# LPC2368_Breakout.net
KiCad netlist of a schematic drawn in EAGLE
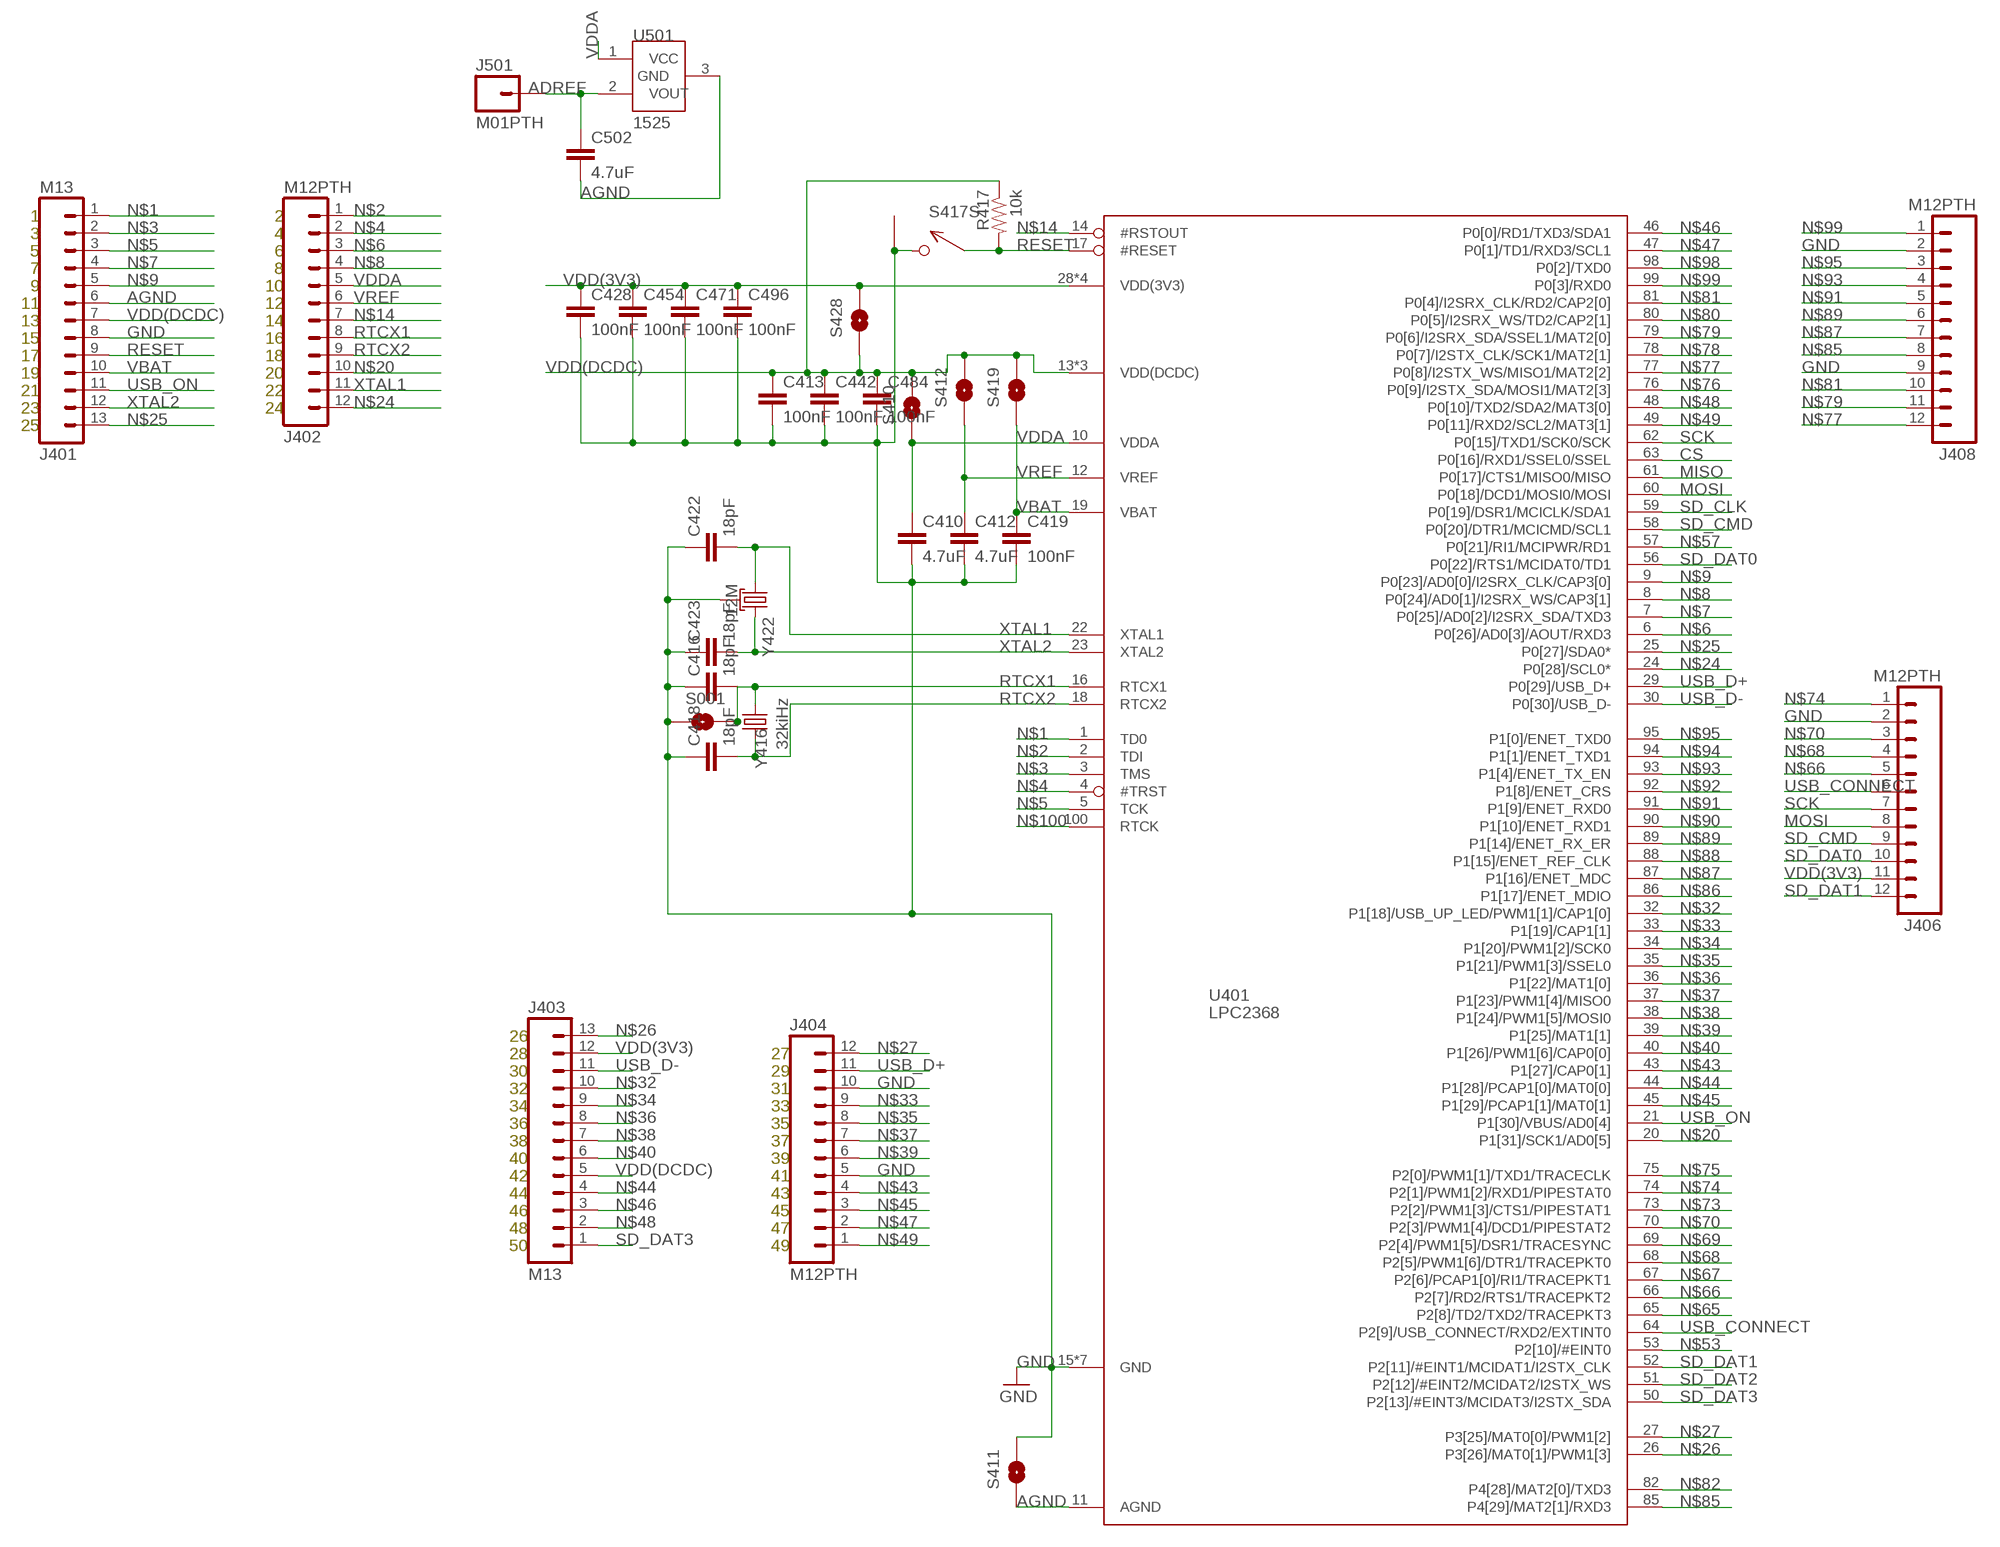
[diagram p0: schematic, sheet 1, part 1 of 2]
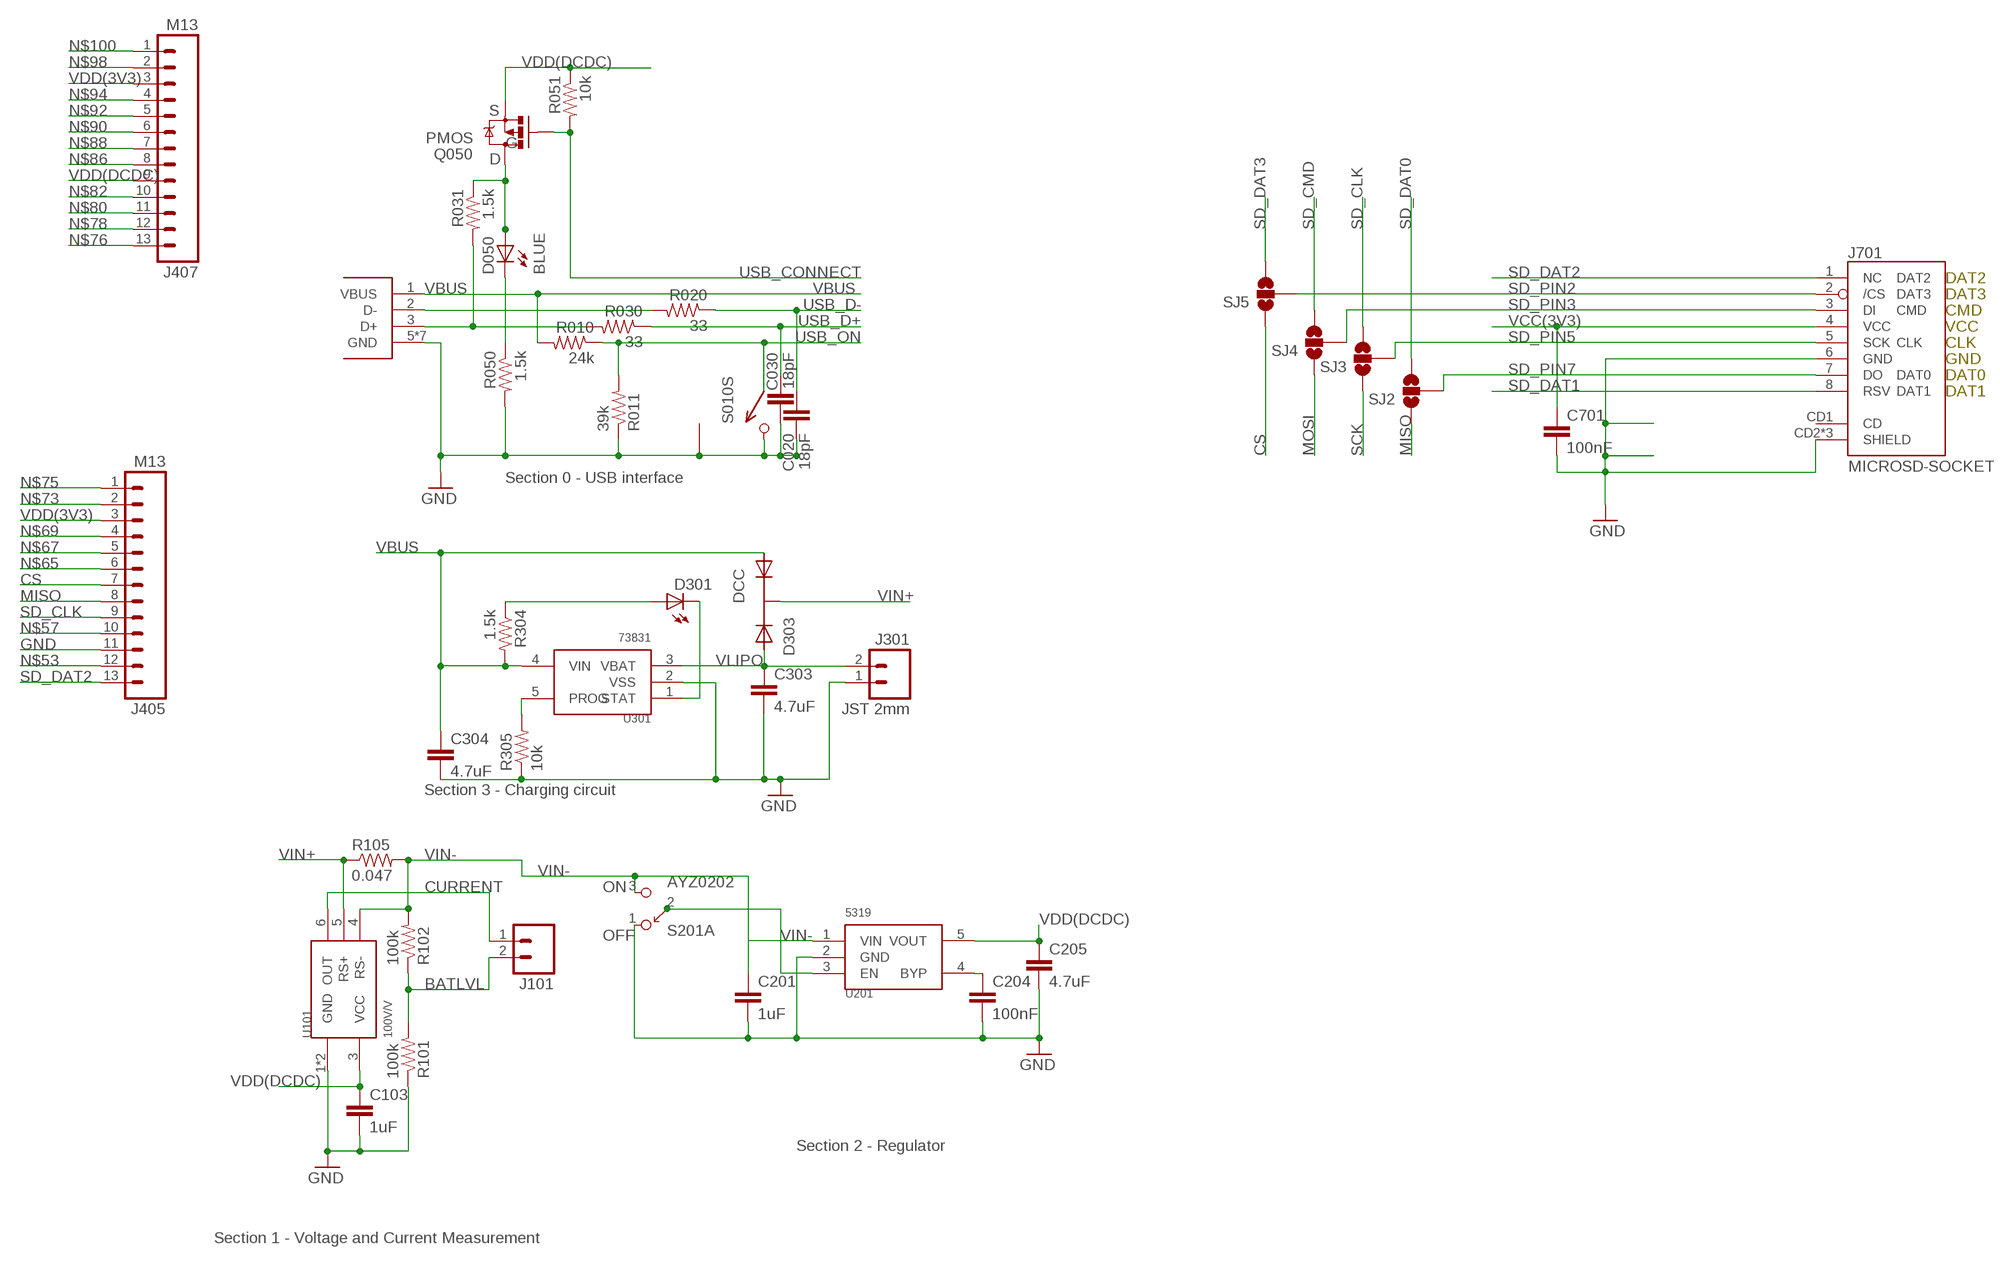
[diagram p1: schematic, sheet 1, part 2 of 2]

(export (version "E")
  (design (tool "Eeschema 10.0.6"))
  (components
    (comp (ref "C020")
      (value "18pF")
      (footprint "eagle-import:0402-CAP")
      (libsource (lib "eagle-import") (part "CAP0402-CAP"))
    )
    (comp (ref "C030")
      (value "18pF")
      (footprint "eagle-import:0402-CAP")
      (libsource (lib "eagle-import") (part "CAP0402-CAP"))
    )
    (comp (ref "C103")
      (value "1uF")
      (footprint "eagle-import:0402-CAP")
      (libsource (lib "eagle-import") (part "CAP0402-CAP"))
    )
    (comp (ref "C201")
      (value "1uF")
      (footprint "eagle-import:0402-CAP")
      (libsource (lib "eagle-import") (part "CAP0402-CAP"))
    )
    (comp (ref "C204")
      (value "100nF")
      (footprint "eagle-import:0402-CAP")
      (libsource (lib "eagle-import") (part "CAP0402-CAP"))
    )
    (comp (ref "C205")
      (value "4.7uF")
      (footprint "eagle-import:0402-CAP")
      (libsource (lib "eagle-import") (part "CAP0402-CAP"))
    )
    (comp (ref "C303")
      (value "4.7uF")
      (footprint "eagle-import:0402-CAP")
      (libsource (lib "eagle-import") (part "CAP0402-CAP"))
    )
    (comp (ref "C304")
      (value "4.7uF")
      (footprint "eagle-import:0402-CAP")
      (libsource (lib "eagle-import") (part "CAP0402-CAP"))
    )
    (comp (ref "C410")
      (value "4.7uF")
      (footprint "eagle-import:0402-CAP")
      (libsource (lib "eagle-import") (part "SparkFun-Passives_CAP0402-CAP"))
    )
    (comp (ref "C412")
      (value "4.7uF")
      (footprint "eagle-import:0402-CAP")
      (libsource (lib "eagle-import") (part "SparkFun-Passives_CAP0402-CAP"))
    )
    (comp (ref "C413")
      (value "100nF")
      (footprint "eagle-import:0402-CAP")
      (libsource (lib "eagle-import") (part "SparkFun-Passives_CAP0402-CAP"))
    )
    (comp (ref "C416")
      (value "18pF")
      (footprint "eagle-import:0402-CAP")
      (libsource (lib "eagle-import") (part "SparkFun-Passives_CAP0402-CAP"))
    )
    (comp (ref "C418")
      (value "18pF")
      (footprint "eagle-import:0402-CAP")
      (libsource (lib "eagle-import") (part "SparkFun-Passives_CAP0402-CAP"))
    )
    (comp (ref "C419")
      (value "100nF")
      (footprint "eagle-import:0402-CAP")
      (libsource (lib "eagle-import") (part "SparkFun-Passives_CAP0402-CAP"))
    )
    (comp (ref "C422")
      (value "18pF")
      (footprint "eagle-import:0402-CAP")
      (libsource (lib "eagle-import") (part "SparkFun-Passives_CAP0402-CAP"))
    )
    (comp (ref "C423")
      (value "18pF")
      (footprint "eagle-import:0402-CAP")
      (libsource (lib "eagle-import") (part "SparkFun-Passives_CAP0402-CAP"))
    )
    (comp (ref "C428")
      (value "100nF")
      (footprint "eagle-import:0402-CAP")
      (libsource (lib "eagle-import") (part "SparkFun-Passives_CAP0402-CAP"))
    )
    (comp (ref "C442")
      (value "100nF")
      (footprint "eagle-import:0402-CAP")
      (libsource (lib "eagle-import") (part "SparkFun-Passives_CAP0402-CAP"))
    )
    (comp (ref "C454")
      (value "100nF")
      (footprint "eagle-import:0402-CAP")
      (libsource (lib "eagle-import") (part "SparkFun-Passives_CAP0402-CAP"))
    )
    (comp (ref "C471")
      (value "100nF")
      (footprint "eagle-import:0402-CAP")
      (libsource (lib "eagle-import") (part "SparkFun-Passives_CAP0402-CAP"))
    )
    (comp (ref "C484")
      (value "100nF")
      (footprint "eagle-import:0402-CAP")
      (libsource (lib "eagle-import") (part "SparkFun-Passives_CAP0402-CAP"))
    )
    (comp (ref "C496")
      (value "100nF")
      (footprint "eagle-import:0402-CAP")
      (libsource (lib "eagle-import") (part "SparkFun-Passives_CAP0402-CAP"))
    )
    (comp (ref "C502")
      (value "4.7uF")
      (footprint "eagle-import:0402-CAP")
      (libsource (lib "eagle-import") (part "CAP0402-CAP"))
    )
    (comp (ref "C701")
      (value "100nF")
      (footprint "eagle-import:0402-CAP")
      (libsource (lib "eagle-import") (part "CAP0402-CAP"))
    )
    (comp (ref "D050")
      (value "BLUE")
      (footprint "eagle-import:LED-0603")
      (libsource (lib "eagle-import") (part "LED0603"))
    )
    (comp (ref "D301")
      (value "YELLOW")
      (footprint "eagle-import:LED-0603")
      (libsource (lib "eagle-import") (part "LED0603"))
    )
    (comp (ref "D303")
      (value "DCC")
      (footprint "eagle-import:SOT-23-3")
      (libsource (lib "eagle-import") (part "PMEG2005CT"))
    )
    (comp (ref "J001")
      (value "USB_MICROB_JST")
      (footprint "eagle-import:UB-MC5BR3-SD204-4S")
      (libsource (lib "eagle-import") (part "USB_MICROB_JST"))
    )
    (comp (ref "J101")
      (value "M02PTH")
      (footprint "eagle-import:1X02")
      (libsource (lib "eagle-import") (part "SparkFun-Connectors_M02PTH"))
    )
    (comp (ref "J301")
      (value "JST 2mm")
      (footprint "eagle-import:JST-2-SMD")
      (libsource (lib "eagle-import") (part "M02-JST-2MM-SMT"))
    )
    (comp (ref "J401")
      (value "M13")
      (footprint "eagle-import:1X13")
      (libsource (lib "eagle-import") (part "M13"))
    )
    (comp (ref "J402")
      (value "M12PTH")
      (footprint "eagle-import:1X12")
      (libsource (lib "eagle-import") (part "M12PTH"))
    )
    (comp (ref "J403")
      (value "M13")
      (footprint "eagle-import:1X13")
      (libsource (lib "eagle-import") (part "M13"))
    )
    (comp (ref "J404")
      (value "M12PTH")
      (footprint "eagle-import:1X12")
      (libsource (lib "eagle-import") (part "M12PTH"))
    )
    (comp (ref "J405")
      (value "M13")
      (footprint "eagle-import:1X13")
      (libsource (lib "eagle-import") (part "M13"))
    )
    (comp (ref "J406")
      (value "M12PTH")
      (footprint "eagle-import:1X12")
      (libsource (lib "eagle-import") (part "M12PTH"))
    )
    (comp (ref "J407")
      (value "M13")
      (footprint "eagle-import:1X13")
      (libsource (lib "eagle-import") (part "M13"))
    )
    (comp (ref "J408")
      (value "M12PTH")
      (footprint "eagle-import:1X12")
      (libsource (lib "eagle-import") (part "M12PTH"))
    )
    (comp (ref "J501")
      (value "M01PTH")
      (footprint "eagle-import:1X01")
      (libsource (lib "eagle-import") (part "M01PTH"))
    )
    (comp (ref "J701")
      (value "MICROSD-SOCKET")
      (footprint "eagle-import:MICROSD-SOCKET-PP")
      (libsource (lib "eagle-import") (part "MICROSD-SOCKET"))
    )
    (comp (ref "Q050")
      (value "PMOS")
      (footprint "eagle-import:SOT23-3")
      (libsource (lib "eagle-import") (part "MOSFET-PCHANNELSMD"))
    )
    (comp (ref "R010")
      (value "24k")
      (footprint "eagle-import:0402-RES")
      (libsource (lib "eagle-import") (part "RESISTOR0402-RES"))
    )
    (comp (ref "R011")
      (value "39k")
      (footprint "eagle-import:0402-RES")
      (libsource (lib "eagle-import") (part "RESISTOR0402-RES"))
    )
    (comp (ref "R020")
      (value "33")
      (footprint "eagle-import:0402-RES")
      (libsource (lib "eagle-import") (part "RESISTOR0402-RES"))
    )
    (comp (ref "R030")
      (value "33")
      (footprint "eagle-import:0402-RES")
      (libsource (lib "eagle-import") (part "RESISTOR0402-RES"))
    )
    (comp (ref "R031")
      (value "1.5k")
      (footprint "eagle-import:0402-RES")
      (libsource (lib "eagle-import") (part "RESISTOR0402-RES"))
    )
    (comp (ref "R050")
      (value "1.5k")
      (footprint "eagle-import:0402-RES")
      (libsource (lib "eagle-import") (part "RESISTOR0402-RES"))
    )
    (comp (ref "R051")
      (value "10k")
      (footprint "eagle-import:0402-RES")
      (libsource (lib "eagle-import") (part "RESISTOR0402-RES"))
    )
    (comp (ref "R101")
      (value "100k")
      (footprint "eagle-import:0402-RES")
      (libsource (lib "eagle-import") (part "RESISTOR0402-RES"))
    )
    (comp (ref "R102")
      (value "100k")
      (footprint "eagle-import:0402-RES")
      (libsource (lib "eagle-import") (part "RESISTOR0402-RES"))
    )
    (comp (ref "R105")
      (value "0.047")
      (footprint "eagle-import:0402-RES")
      (libsource (lib "eagle-import") (part "RESISTOR0402-RES"))
    )
    (comp (ref "R304")
      (value "1.5k")
      (footprint "eagle-import:0402-RES")
      (libsource (lib "eagle-import") (part "RESISTOR0402-RES"))
    )
    (comp (ref "R305")
      (value "10k")
      (footprint "eagle-import:0402-RES")
      (libsource (lib "eagle-import") (part "RESISTOR0402-RES"))
    )
    (comp (ref "R417")
      (value "10k")
      (footprint "eagle-import:0402-RES")
      (libsource (lib "eagle-import") (part "RESISTOR0402-RES"))
    )
    (comp (ref "S001")
      (value "SOLDERJUMPERNO")
      (footprint "eagle-import:SJ_2S-NO")
      (libsource (lib "eagle-import") (part "SOLDERJUMPERNO"))
    )
    (comp (ref "S010")
      (value "SPST")
      (footprint "eagle-import:B3U-1100P")
      (libsource (lib "eagle-import") (part "B3U-1100P"))
    )
    (comp (ref "S201")
      (value "AYZ0202")
      (footprint "eagle-import:AYZ0202")
      (libsource (lib "eagle-import") (part "AYZ0202"))
    )
    (comp (ref "S410")
      (value "SOLDERJUMPERNO")
      (footprint "eagle-import:SJ_2S-NO")
      (libsource (lib "eagle-import") (part "SOLDERJUMPERNO"))
    )
    (comp (ref "S411")
      (value "SOLDERJUMPERNO")
      (footprint "eagle-import:SJ_2S-NO")
      (libsource (lib "eagle-import") (part "SOLDERJUMPERNO"))
    )
    (comp (ref "S412")
      (value "SOLDERJUMPERNO")
      (footprint "eagle-import:SJ_2S-NO")
      (libsource (lib "eagle-import") (part "SOLDERJUMPERNO"))
    )
    (comp (ref "S417")
      (value "SPST")
      (footprint "eagle-import:B3U-1100P")
      (libsource (lib "eagle-import") (part "B3U-1100P"))
    )
    (comp (ref "S419")
      (value "SOLDERJUMPERNO")
      (footprint "eagle-import:SJ_2S-NO")
      (libsource (lib "eagle-import") (part "SOLDERJUMPERNO"))
    )
    (comp (ref "S428")
      (value "SOLDERJUMPERNO")
      (footprint "eagle-import:SJ_2S-NO")
      (libsource (lib "eagle-import") (part "SOLDERJUMPERNO"))
    )
    (comp (ref "SJ2")
      (value "SOLDERJUMPER_2WAYS")
      (footprint "eagle-import:SJ_3")
      (libsource (lib "eagle-import") (part "SOLDERJUMPER_2WAYS"))
    )
    (comp (ref "SJ3")
      (value "SOLDERJUMPER_2WAYS")
      (footprint "eagle-import:SJ_3")
      (libsource (lib "eagle-import") (part "SOLDERJUMPER_2WAYS"))
    )
    (comp (ref "SJ4")
      (value "SOLDERJUMPER_2WAYS")
      (footprint "eagle-import:SJ_3")
      (libsource (lib "eagle-import") (part "SOLDERJUMPER_2WAYS"))
    )
    (comp (ref "SJ5")
      (value "SOLDERJUMPER_2WAYS")
      (footprint "eagle-import:SJ_3")
      (libsource (lib "eagle-import") (part "SOLDERJUMPER_2WAYS"))
    )
    (comp (ref "U101")
      (value "100V/V")
      (footprint "eagle-import:SOT-23-6")
      (libsource (lib "eagle-import") (part "MAX4173"))
    )
    (comp (ref "U201")
      (value "5319")
      (footprint "eagle-import:SOT-23-5")
      (libsource (lib "eagle-import") (part "MIC5319D5"))
    )
    (comp (ref "U301")
      (value "73831")
      (footprint "eagle-import:SOT-23-5")
      (libsource (lib "eagle-import") (part "MCP73831"))
    )
    (comp (ref "U401")
      (value "LPC2368")
      (footprint "eagle-import:LQFP100")
      (libsource (lib "eagle-import") (part "LPC2368"))
    )
    (comp (ref "U501")
      (value "1525")
      (footprint "eagle-import:SOT-23-3")
      (libsource (lib "eagle-import") (part "MCP1525"))
    )
    (comp (ref "Y416")
      (value "32kiHz")
      (footprint "eagle-import:ABS06")
      (libsource (lib "eagle-import") (part "ABS06"))
    )
    (comp (ref "Y422")
      (value "12M")
      (footprint "eagle-import:CRYSTAL_SMD")
      (libsource (lib "eagle-import") (part "TSX-3225"))
    )
  )
  (nets
    (net (code "1") (name "/ADREF") (class "Default")
      (node (ref "C502") (pin "1") (pinfunction "1_1") (pintype "passive"))
      (node (ref "J501") (pin "1") (pinfunction "1_1") (pintype "passive"))
      (node (ref "U501") (pin "2") (pinfunction "VOUT_2") (pintype "bidirectional"))
    )
    (net (code "2") (name "/AGND") (class "Default")
      (node (ref "C502") (pin "2") (pinfunction "2_2") (pintype "passive"))
      (node (ref "J401") (pin "6") (pinfunction "6_6") (pintype "passive"))
      (node (ref "S411") (pin "1") (pinfunction "1_1") (pintype "passive"))
      (node (ref "U401") (pin "11") (pinfunction "AGND_11") (pintype "bidirectional"))
      (node (ref "U501") (pin "3") (pinfunction "GND_3") (pintype "bidirectional"))
    )
    (net (code "3") (name "/BATLVL") (class "Default")
      (node (ref "J101") (pin "2") (pinfunction "2_2") (pintype "passive"))
      (node (ref "R101") (pin "2") (pinfunction "2_2") (pintype "passive"))
      (node (ref "R102") (pin "1") (pinfunction "1_1") (pintype "passive"))
    )
    (net (code "4") (name "/CS") (class "Default")
      (node (ref "J405") (pin "7") (pinfunction "7_7") (pintype "passive"))
      (node (ref "SJ5") (pin "1") (pinfunction "1_1") (pintype "passive"))
      (node (ref "U401") (pin "63") (pinfunction "P0[16]/RXD1/SSEL0/SSEL_63") (pintype "bidirectional"))
    )
    (net (code "5") (name "/CURRENT") (class "Default")
      (node (ref "J101") (pin "1") (pinfunction "1_1") (pintype "passive"))
      (node (ref "U101") (pin "6") (pinfunction "OUT_6") (pintype "bidirectional"))
    )
    (net (code "6") (name "/MISO") (class "Default")
      (node (ref "J405") (pin "8") (pinfunction "8_8") (pintype "passive"))
      (node (ref "SJ2") (pin "1") (pinfunction "1_1") (pintype "passive"))
      (node (ref "U401") (pin "61") (pinfunction "P0[17]/CTS1/MISO0/MISO_61") (pintype "bidirectional"))
    )
    (net (code "7") (name "/MOSI") (class "Default")
      (node (ref "J406") (pin "8") (pinfunction "8_8") (pintype "passive"))
      (node (ref "SJ4") (pin "1") (pinfunction "1_1") (pintype "passive"))
      (node (ref "U401") (pin "60") (pinfunction "P0[18]/DCD1/MOSI0/MOSI_60") (pintype "bidirectional"))
    )
    (net (code "8") (name "/N$1") (class "Default")
      (node (ref "J401") (pin "1") (pinfunction "1_1") (pintype "passive"))
      (node (ref "U401") (pin "1") (pinfunction "TD0_1") (pintype "bidirectional"))
    )
    (net (code "9") (name "/N$2") (class "Default")
      (node (ref "J402") (pin "1") (pinfunction "1_1") (pintype "passive"))
      (node (ref "U401") (pin "2") (pinfunction "TDI_2") (pintype "bidirectional"))
    )
    (net (code "10") (name "/N$3") (class "Default")
      (node (ref "J401") (pin "2") (pinfunction "2_2") (pintype "passive"))
      (node (ref "U401") (pin "3") (pinfunction "TMS_3") (pintype "bidirectional"))
    )
    (net (code "11") (name "/N$4") (class "Default")
      (node (ref "J402") (pin "2") (pinfunction "2_2") (pintype "passive"))
      (node (ref "U401") (pin "4") (pinfunction "#TRST_4") (pintype "bidirectional"))
    )
    (net (code "12") (name "/N$5") (class "Default")
      (node (ref "J401") (pin "3") (pinfunction "3_3") (pintype "passive"))
      (node (ref "U401") (pin "5") (pinfunction "TCK_5") (pintype "bidirectional"))
    )
    (net (code "13") (name "/N$6") (class "Default")
      (node (ref "J402") (pin "3") (pinfunction "3_3") (pintype "passive"))
      (node (ref "U401") (pin "6") (pinfunction "P0[26]/AD0[3]/AOUT/RXD3_6") (pintype "bidirectional"))
    )
    (net (code "14") (name "/N$7") (class "Default")
      (node (ref "J401") (pin "4") (pinfunction "4_4") (pintype "passive"))
      (node (ref "U401") (pin "7") (pinfunction "P0[25]/AD0[2]/I2SRX_SDA/TXD3_7") (pintype "bidirectional"))
    )
    (net (code "15") (name "/N$8") (class "Default")
      (node (ref "J402") (pin "4") (pinfunction "4_4") (pintype "passive"))
      (node (ref "U401") (pin "8") (pinfunction "P0[24]/AD0[1]/I2SRX_WS/CAP3[1]_8") (pintype "bidirectional"))
    )
    (net (code "16") (name "/N$9") (class "Default")
      (node (ref "J401") (pin "5") (pinfunction "5_5") (pintype "passive"))
      (node (ref "U401") (pin "9") (pinfunction "P0[23]/AD0[0]/I2SRX_CLK/CAP3[0]_9") (pintype "bidirectional"))
    )
    (net (code "17") (name "/N$14") (class "Default")
      (node (ref "J402") (pin "7") (pinfunction "7_7") (pintype "passive"))
      (node (ref "U401") (pin "14") (pinfunction "#RSTOUT_14") (pintype "bidirectional"))
    )
    (net (code "18") (name "/N$20") (class "Default")
      (node (ref "J402") (pin "10") (pinfunction "10_10") (pintype "passive"))
      (node (ref "U401") (pin "20") (pinfunction "P1[31]/SCK1/AD0[5]_20") (pintype "bidirectional"))
    )
    (net (code "19") (name "/N$24") (class "Default")
      (node (ref "J402") (pin "12") (pinfunction "12_12") (pintype "passive"))
      (node (ref "U401") (pin "24") (pinfunction "P0[28]/SCL0*_24") (pintype "bidirectional"))
    )
    (net (code "20") (name "/N$25") (class "Default")
      (node (ref "J401") (pin "13") (pinfunction "13_13") (pintype "passive"))
      (node (ref "U401") (pin "25") (pinfunction "P0[27]/SDA0*_25") (pintype "bidirectional"))
    )
    (net (code "21") (name "/N$26") (class "Default")
      (node (ref "J403") (pin "13") (pinfunction "13_13") (pintype "passive"))
      (node (ref "U401") (pin "26") (pinfunction "P3[26]/MAT0[1]/PWM1[3]_26") (pintype "bidirectional"))
    )
    (net (code "22") (name "/N$27") (class "Default")
      (node (ref "J404") (pin "12") (pinfunction "12_12") (pintype "passive"))
      (node (ref "U401") (pin "27") (pinfunction "P3[25]/MAT0[0]/PWM1[2]_27") (pintype "bidirectional"))
    )
    (net (code "23") (name "/N$32") (class "Default")
      (node (ref "J403") (pin "10") (pinfunction "10_10") (pintype "passive"))
      (node (ref "U401") (pin "32") (pinfunction "P1[18]/USB_UP_LED/PWM1[1]/CAP1[0]_32") (pintype "bidirectional"))
    )
    (net (code "24") (name "/N$33") (class "Default")
      (node (ref "J404") (pin "9") (pinfunction "9_9") (pintype "passive"))
      (node (ref "U401") (pin "33") (pinfunction "P1[19]/CAP1[1]_33") (pintype "bidirectional"))
    )
    (net (code "25") (name "/N$34") (class "Default")
      (node (ref "J403") (pin "9") (pinfunction "9_9") (pintype "passive"))
      (node (ref "U401") (pin "34") (pinfunction "P1[20]/PWM1[2]/SCK0_34") (pintype "bidirectional"))
    )
    (net (code "26") (name "/N$35") (class "Default")
      (node (ref "J404") (pin "8") (pinfunction "8_8") (pintype "passive"))
      (node (ref "U401") (pin "35") (pinfunction "P1[21]/PWM1[3]/SSEL0_35") (pintype "bidirectional"))
    )
    (net (code "27") (name "/N$36") (class "Default")
      (node (ref "J403") (pin "8") (pinfunction "8_8") (pintype "passive"))
      (node (ref "U401") (pin "36") (pinfunction "P1[22]/MAT1[0]_36") (pintype "bidirectional"))
    )
    (net (code "28") (name "/N$37") (class "Default")
      (node (ref "J404") (pin "7") (pinfunction "7_7") (pintype "passive"))
      (node (ref "U401") (pin "37") (pinfunction "P1[23]/PWM1[4]/MISO0_37") (pintype "bidirectional"))
    )
    (net (code "29") (name "/N$38") (class "Default")
      (node (ref "J403") (pin "7") (pinfunction "7_7") (pintype "passive"))
      (node (ref "U401") (pin "38") (pinfunction "P1[24]/PWM1[5]/MOSI0_38") (pintype "bidirectional"))
    )
    (net (code "30") (name "/N$39") (class "Default")
      (node (ref "J404") (pin "6") (pinfunction "6_6") (pintype "passive"))
      (node (ref "U401") (pin "39") (pinfunction "P1[25]/MAT1[1]_39") (pintype "bidirectional"))
    )
    (net (code "31") (name "/N$40") (class "Default")
      (node (ref "J403") (pin "6") (pinfunction "6_6") (pintype "passive"))
      (node (ref "U401") (pin "40") (pinfunction "P1[26]/PWM1[6]/CAP0[0]_40") (pintype "bidirectional"))
    )
    (net (code "32") (name "/N$43") (class "Default")
      (node (ref "J404") (pin "4") (pinfunction "4_4") (pintype "passive"))
      (node (ref "U401") (pin "43") (pinfunction "P1[27]/CAP0[1]_43") (pintype "bidirectional"))
    )
    (net (code "33") (name "/N$44") (class "Default")
      (node (ref "J403") (pin "4") (pinfunction "4_4") (pintype "passive"))
      (node (ref "U401") (pin "44") (pinfunction "P1[28]/PCAP1[0]/MAT0[0]_44") (pintype "bidirectional"))
    )
    (net (code "34") (name "/N$45") (class "Default")
      (node (ref "J404") (pin "3") (pinfunction "3_3") (pintype "passive"))
      (node (ref "U401") (pin "45") (pinfunction "P1[29]/PCAP1[1]/MAT0[1]_45") (pintype "bidirectional"))
    )
    (net (code "35") (name "/N$46") (class "Default")
      (node (ref "J403") (pin "3") (pinfunction "3_3") (pintype "passive"))
      (node (ref "U401") (pin "46") (pinfunction "P0[0]/RD1/TXD3/SDA1_46") (pintype "bidirectional"))
    )
    (net (code "36") (name "/N$47") (class "Default")
      (node (ref "J404") (pin "2") (pinfunction "2_2") (pintype "passive"))
      (node (ref "U401") (pin "47") (pinfunction "P0[1]/TD1/RXD3/SCL1_47") (pintype "bidirectional"))
    )
    (net (code "37") (name "/N$48") (class "Default")
      (node (ref "J403") (pin "2") (pinfunction "2_2") (pintype "passive"))
      (node (ref "U401") (pin "48") (pinfunction "P0[10]/TXD2/SDA2/MAT3[0]_48") (pintype "bidirectional"))
    )
    (net (code "38") (name "/N$49") (class "Default")
      (node (ref "J404") (pin "1") (pinfunction "1_1") (pintype "passive"))
      (node (ref "U401") (pin "49") (pinfunction "P0[11]/RXD2/SCL2/MAT3[1]_49") (pintype "bidirectional"))
    )
    (net (code "39") (name "/N$53") (class "Default")
      (node (ref "J405") (pin "12") (pinfunction "12_12") (pintype "passive"))
      (node (ref "U401") (pin "53") (pinfunction "P2[10]/#EINT0_53") (pintype "bidirectional"))
    )
    (net (code "40") (name "/N$57") (class "Default")
      (node (ref "J405") (pin "10") (pinfunction "10_10") (pintype "passive"))
      (node (ref "U401") (pin "57") (pinfunction "P0[21]/RI1/MCIPWR/RD1_57") (pintype "bidirectional"))
    )
    (net (code "41") (name "/N$65") (class "Default")
      (node (ref "J405") (pin "6") (pinfunction "6_6") (pintype "passive"))
      (node (ref "U401") (pin "65") (pinfunction "P2[8]/TD2/TXD2/TRACEPKT3_65") (pintype "bidirectional"))
    )
    (net (code "42") (name "/N$66") (class "Default")
      (node (ref "J406") (pin "5") (pinfunction "5_5") (pintype "passive"))
      (node (ref "U401") (pin "66") (pinfunction "P2[7]/RD2/RTS1/TRACEPKT2_66") (pintype "bidirectional"))
    )
    (net (code "43") (name "/N$67") (class "Default")
      (node (ref "J405") (pin "5") (pinfunction "5_5") (pintype "passive"))
      (node (ref "U401") (pin "67") (pinfunction "P2[6]/PCAP1[0]/RI1/TRACEPKT1_67") (pintype "bidirectional"))
    )
    (net (code "44") (name "/N$68") (class "Default")
      (node (ref "J406") (pin "4") (pinfunction "4_4") (pintype "passive"))
      (node (ref "U401") (pin "68") (pinfunction "P2[5]/PWM1[6]/DTR1/TRACEPKT0_68") (pintype "bidirectional"))
    )
    (net (code "45") (name "/N$69") (class "Default")
      (node (ref "J405") (pin "4") (pinfunction "4_4") (pintype "passive"))
      (node (ref "U401") (pin "69") (pinfunction "P2[4]/PWM1[5]/DSR1/TRACESYNC_69") (pintype "bidirectional"))
    )
    (net (code "46") (name "/N$70") (class "Default")
      (node (ref "J406") (pin "3") (pinfunction "3_3") (pintype "passive"))
      (node (ref "U401") (pin "70") (pinfunction "P2[3]/PWM1[4]/DCD1/PIPESTAT2_70") (pintype "bidirectional"))
    )
    (net (code "47") (name "/N$73") (class "Default")
      (node (ref "J405") (pin "2") (pinfunction "2_2") (pintype "passive"))
      (node (ref "U401") (pin "73") (pinfunction "P2[2]/PWM1[3]/CTS1/PIPESTAT1_73") (pintype "bidirectional"))
    )
    (net (code "48") (name "/N$74") (class "Default")
      (node (ref "J406") (pin "1") (pinfunction "1_1") (pintype "passive"))
      (node (ref "U401") (pin "74") (pinfunction "P2[1]/PWM1[2]/RXD1/PIPESTAT0_74") (pintype "bidirectional"))
    )
    (net (code "49") (name "/N$75") (class "Default")
      (node (ref "J405") (pin "1") (pinfunction "1_1") (pintype "passive"))
      (node (ref "U401") (pin "75") (pinfunction "P2[0]/PWM1[1]/TXD1/TRACECLK_75") (pintype "bidirectional"))
    )
    (net (code "50") (name "/N$76") (class "Default")
      (node (ref "J407") (pin "13") (pinfunction "13_13") (pintype "passive"))
      (node (ref "U401") (pin "76") (pinfunction "P0[9]/I2STX_SDA/MOSI1/MAT2[3]_76") (pintype "bidirectional"))
    )
    (net (code "51") (name "/N$77") (class "Default")
      (node (ref "J408") (pin "12") (pinfunction "12_12") (pintype "passive"))
      (node (ref "U401") (pin "77") (pinfunction "P0[8]/I2STX_WS/MISO1/MAT2[2]_77") (pintype "bidirectional"))
    )
    (net (code "52") (name "/N$78") (class "Default")
      (node (ref "J407") (pin "12") (pinfunction "12_12") (pintype "passive"))
      (node (ref "U401") (pin "78") (pinfunction "P0[7]/I2STX_CLK/SCK1/MAT2[1]_78") (pintype "bidirectional"))
    )
    (net (code "53") (name "/N$79") (class "Default")
      (node (ref "J408") (pin "11") (pinfunction "11_11") (pintype "passive"))
      (node (ref "U401") (pin "79") (pinfunction "P0[6]/I2SRX_SDA/SSEL1/MAT2[0]_79") (pintype "bidirectional"))
    )
    (net (code "54") (name "/N$80") (class "Default")
      (node (ref "J407") (pin "11") (pinfunction "11_11") (pintype "passive"))
      (node (ref "U401") (pin "80") (pinfunction "P0[5]/I2SRX_WS/TD2/CAP2[1]_80") (pintype "bidirectional"))
    )
    (net (code "55") (name "/N$81") (class "Default")
      (node (ref "J408") (pin "10") (pinfunction "10_10") (pintype "passive"))
      (node (ref "U401") (pin "81") (pinfunction "P0[4]/I2SRX_CLK/RD2/CAP2[0]_81") (pintype "bidirectional"))
    )
    (net (code "56") (name "/N$82") (class "Default")
      (node (ref "J407") (pin "10") (pinfunction "10_10") (pintype "passive"))
      (node (ref "U401") (pin "82") (pinfunction "P4[28]/MAT2[0]/TXD3_82") (pintype "bidirectional"))
    )
    (net (code "57") (name "/N$85") (class "Default")
      (node (ref "J408") (pin "8") (pinfunction "8_8") (pintype "passive"))
      (node (ref "U401") (pin "85") (pinfunction "P4[29]/MAT2[1]/RXD3_85") (pintype "bidirectional"))
    )
    (net (code "58") (name "/N$86") (class "Default")
      (node (ref "J407") (pin "8") (pinfunction "8_8") (pintype "passive"))
      (node (ref "U401") (pin "86") (pinfunction "P1[17]/ENET_MDIO_86") (pintype "bidirectional"))
    )
    (net (code "59") (name "/N$87") (class "Default")
      (node (ref "J408") (pin "7") (pinfunction "7_7") (pintype "passive"))
      (node (ref "U401") (pin "87") (pinfunction "P1[16]/ENET_MDC_87") (pintype "bidirectional"))
    )
    (net (code "60") (name "/N$88") (class "Default")
      (node (ref "J407") (pin "7") (pinfunction "7_7") (pintype "passive"))
      (node (ref "U401") (pin "88") (pinfunction "P1[15]/ENET_REF_CLK_88") (pintype "bidirectional"))
    )
    (net (code "61") (name "/N$89") (class "Default")
      (node (ref "J408") (pin "6") (pinfunction "6_6") (pintype "passive"))
      (node (ref "U401") (pin "89") (pinfunction "P1[14]/ENET_RX_ER_89") (pintype "bidirectional"))
    )
    (net (code "62") (name "/N$90") (class "Default")
      (node (ref "J407") (pin "6") (pinfunction "6_6") (pintype "passive"))
      (node (ref "U401") (pin "90") (pinfunction "P1[10]/ENET_RXD1_90") (pintype "bidirectional"))
    )
    (net (code "63") (name "/N$91") (class "Default")
      (node (ref "J408") (pin "5") (pinfunction "5_5") (pintype "passive"))
      (node (ref "U401") (pin "91") (pinfunction "P1[9]/ENET_RXD0_91") (pintype "bidirectional"))
    )
    (net (code "64") (name "/N$92") (class "Default")
      (node (ref "J407") (pin "5") (pinfunction "5_5") (pintype "passive"))
      (node (ref "U401") (pin "92") (pinfunction "P1[8]/ENET_CRS_92") (pintype "bidirectional"))
    )
    (net (code "65") (name "/N$93") (class "Default")
      (node (ref "J408") (pin "4") (pinfunction "4_4") (pintype "passive"))
      (node (ref "U401") (pin "93") (pinfunction "P1[4]/ENET_TX_EN_93") (pintype "bidirectional"))
    )
    (net (code "66") (name "/N$94") (class "Default")
      (node (ref "J407") (pin "4") (pinfunction "4_4") (pintype "passive"))
      (node (ref "U401") (pin "94") (pinfunction "P1[1]/ENET_TXD1_94") (pintype "bidirectional"))
    )
    (net (code "67") (name "/N$95") (class "Default")
      (node (ref "J408") (pin "3") (pinfunction "3_3") (pintype "passive"))
      (node (ref "U401") (pin "95") (pinfunction "P1[0]/ENET_TXD0_95") (pintype "bidirectional"))
    )
    (net (code "68") (name "/N$98") (class "Default")
      (node (ref "J407") (pin "2") (pinfunction "2_2") (pintype "passive"))
      (node (ref "U401") (pin "98") (pinfunction "P0[2]/TXD0_98") (pintype "bidirectional"))
    )
    (net (code "69") (name "/N$99") (class "Default")
      (node (ref "J408") (pin "1") (pinfunction "1_1") (pintype "passive"))
      (node (ref "U401") (pin "99") (pinfunction "P0[3]/RXD0_99") (pintype "bidirectional"))
    )
    (net (code "70") (name "/N$100") (class "Default")
      (node (ref "J407") (pin "1") (pinfunction "1_1") (pintype "passive"))
      (node (ref "U401") (pin "100") (pinfunction "RTCK_100") (pintype "bidirectional"))
    )
    (net (code "71") (name "/RESET") (class "Default")
      (node (ref "J401") (pin "9") (pinfunction "9_9") (pintype "passive"))
      (node (ref "R417") (pin "2") (pinfunction "2_2") (pintype "passive"))
      (node (ref "S417") (pin "P$1") (pinfunction "1_P$1") (pintype "bidirectional"))
      (node (ref "U401") (pin "17") (pinfunction "#RESET_17") (pintype "bidirectional"))
    )
    (net (code "72") (name "/RTCX1") (class "Default")
      (node (ref "C416") (pin "2") (pinfunction "2_2") (pintype "passive"))
      (node (ref "J402") (pin "8") (pinfunction "8_8") (pintype "passive"))
      (node (ref "S001") (pin "2") (pinfunction "2_2") (pintype "passive"))
      (node (ref "U401") (pin "16") (pinfunction "RTCX1_16") (pintype "bidirectional"))
      (node (ref "Y416") (pin "1") (pinfunction "1_1") (pintype "passive"))
    )
    (net (code "73") (name "/RTCX2") (class "Default")
      (node (ref "C418") (pin "2") (pinfunction "2_2") (pintype "passive"))
      (node (ref "J402") (pin "9") (pinfunction "9_9") (pintype "passive"))
      (node (ref "U401") (pin "18") (pinfunction "RTCX2_18") (pintype "bidirectional"))
      (node (ref "Y416") (pin "2") (pinfunction "2_2") (pintype "passive"))
    )
    (net (code "74") (name "/SCK") (class "Default")
      (node (ref "J406") (pin "7") (pinfunction "7_7") (pintype "passive"))
      (node (ref "SJ3") (pin "1") (pinfunction "1_1") (pintype "passive"))
      (node (ref "U401") (pin "62") (pinfunction "P0[15]/TXD1/SCK0/SCK_62") (pintype "bidirectional"))
    )
    (net (code "75") (name "/SD_CLK") (class "Default")
      (node (ref "J405") (pin "9") (pinfunction "9_9") (pintype "passive"))
      (node (ref "SJ3") (pin "3") (pinfunction "3_3") (pintype "passive"))
      (node (ref "U401") (pin "59") (pinfunction "P0[19]/DSR1/MCICLK/SDA1_59") (pintype "bidirectional"))
    )
    (net (code "76") (name "/SD_CMD") (class "Default")
      (node (ref "J406") (pin "9") (pinfunction "9_9") (pintype "passive"))
      (node (ref "SJ4") (pin "3") (pinfunction "3_3") (pintype "passive"))
      (node (ref "U401") (pin "58") (pinfunction "P0[20]/DTR1/MCICMD/SCL1_58") (pintype "bidirectional"))
    )
    (net (code "77") (name "/SD_DAT0") (class "Default")
      (node (ref "J406") (pin "10") (pinfunction "10_10") (pintype "passive"))
      (node (ref "SJ2") (pin "3") (pinfunction "3_3") (pintype "passive"))
      (node (ref "U401") (pin "56") (pinfunction "P0[22]/RTS1/MCIDAT0/TD1_56") (pintype "bidirectional"))
    )
    (net (code "78") (name "/SD_DAT1") (class "Default")
      (node (ref "J406") (pin "12") (pinfunction "12_12") (pintype "passive"))
      (node (ref "J701") (pin "8") (pinfunction "RSV_8") (pintype "bidirectional"))
      (node (ref "U401") (pin "52") (pinfunction "P2[11]/#EINT1/MCIDAT1/I2STX_CLK_52") (pintype "bidirectional"))
    )
    (net (code "79") (name "/SD_DAT2") (class "Default")
      (node (ref "J405") (pin "13") (pinfunction "13_13") (pintype "passive"))
      (node (ref "J701") (pin "1") (pinfunction "NC_1") (pintype "bidirectional"))
      (node (ref "U401") (pin "51") (pinfunction "P2[12]/#EINT2/MCIDAT2/I2STX_WS_51") (pintype "bidirectional"))
    )
    (net (code "80") (name "/SD_DAT3") (class "Default")
      (node (ref "J403") (pin "1") (pinfunction "1_1") (pintype "passive"))
      (node (ref "SJ5") (pin "3") (pinfunction "3_3") (pintype "passive"))
      (node (ref "U401") (pin "50") (pinfunction "P2[13]/#EINT3/MCIDAT3/I2STX_SDA_50") (pintype "bidirectional"))
    )
    (net (code "81") (name "/SD_PIN2") (class "Default")
      (node (ref "J701") (pin "2") (pinfunction "/CS_2") (pintype "bidirectional"))
      (node (ref "SJ5") (pin "2") (pinfunction "2_2") (pintype "passive"))
    )
    (net (code "82") (name "/SD_PIN3") (class "Default")
      (node (ref "J701") (pin "3") (pinfunction "DI_3") (pintype "bidirectional"))
      (node (ref "SJ4") (pin "2") (pinfunction "2_2") (pintype "passive"))
    )
    (net (code "83") (name "/SD_PIN5") (class "Default")
      (node (ref "J701") (pin "5") (pinfunction "SCK_5") (pintype "bidirectional"))
      (node (ref "SJ3") (pin "2") (pinfunction "2_2") (pintype "passive"))
    )
    (net (code "84") (name "/SD_PIN7") (class "Default")
      (node (ref "J701") (pin "7") (pinfunction "DO_7") (pintype "bidirectional"))
      (node (ref "SJ2") (pin "2") (pinfunction "2_2") (pintype "passive"))
    )
    (net (code "85") (name "/USB_CONNECT") (class "Default")
      (node (ref "J406") (pin "6") (pinfunction "6_6") (pintype "passive"))
      (node (ref "Q050") (pin "1") (pinfunction "G_1") (pintype "passive"))
      (node (ref "R051") (pin "2") (pinfunction "2_2") (pintype "passive"))
      (node (ref "U401") (pin "64") (pinfunction "P2[9]/USB_CONNECT/RXD2/EXTINT0_64") (pintype "bidirectional"))
    )
    (net (code "86") (name "/USB_D+") (class "Default")
      (node (ref "C030") (pin "1") (pinfunction "1_1") (pintype "passive"))
      (node (ref "J404") (pin "11") (pinfunction "11_11") (pintype "passive"))
      (node (ref "R030") (pin "1") (pinfunction "1_1") (pintype "passive"))
      (node (ref "U401") (pin "29") (pinfunction "P0[29]/USB_D+_29") (pintype "bidirectional"))
    )
    (net (code "87") (name "/USB_D-") (class "Default")
      (node (ref "C020") (pin "1") (pinfunction "1_1") (pintype "passive"))
      (node (ref "J403") (pin "11") (pinfunction "11_11") (pintype "passive"))
      (node (ref "R020") (pin "1") (pinfunction "1_1") (pintype "passive"))
      (node (ref "U401") (pin "30") (pinfunction "P0[30]/USB_D-_30") (pintype "bidirectional"))
    )
    (net (code "88") (name "/USB_ON") (class "Default")
      (node (ref "J401") (pin "11") (pinfunction "11_11") (pintype "passive"))
      (node (ref "R010") (pin "1") (pinfunction "1_1") (pintype "passive"))
      (node (ref "R011") (pin "2") (pinfunction "2_2") (pintype "passive"))
      (node (ref "S010") (pin "P$1") (pinfunction "1_P$1") (pintype "bidirectional"))
      (node (ref "U401") (pin "21") (pinfunction "P1[30]/VBUS/AD0[4]_21") (pintype "bidirectional"))
    )
    (net (code "89") (name "/VBAT") (class "Default")
      (node (ref "C419") (pin "1") (pinfunction "1_1") (pintype "passive"))
      (node (ref "J401") (pin "10") (pinfunction "10_10") (pintype "passive"))
      (node (ref "S419") (pin "1") (pinfunction "1_1") (pintype "passive"))
      (node (ref "U401") (pin "19") (pinfunction "VBAT_19") (pintype "bidirectional"))
    )
    (net (code "90") (name "/VBUS") (class "Default")
      (node (ref "C304") (pin "1") (pinfunction "1_1") (pintype "passive"))
      (node (ref "D303") (pin "1") (pinfunction "A1_1") (pintype "passive"))
      (node (ref "J001") (pin "1") (pinfunction "VBUS_1") (pintype "bidirectional"))
      (node (ref "R010") (pin "2") (pinfunction "2_2") (pintype "passive"))
      (node (ref "R304") (pin "2") (pinfunction "2_2") (pintype "passive"))
      (node (ref "U301") (pin "4") (pinfunction "VIN_4") (pintype "power_in"))
    )
    (net (code "91") (name "/VCC(3V3)") (class "Default")
      (node (ref "C701") (pin "1") (pinfunction "1_1") (pintype "passive"))
      (node (ref "J701") (pin "4") (pinfunction "VCC_4") (pintype "bidirectional"))
    )
    (net (code "92") (name "/VDD(3V3)") (class "Default")
      (node (ref "C428") (pin "1") (pinfunction "1_1") (pintype "passive"))
      (node (ref "C454") (pin "1") (pinfunction "1_1") (pintype "passive"))
      (node (ref "C471") (pin "1") (pinfunction "1_1") (pintype "passive"))
      (node (ref "C496") (pin "1") (pinfunction "1_1") (pintype "passive"))
      (node (ref "J403") (pin "12") (pinfunction "12_12") (pintype "passive"))
      (node (ref "J405") (pin "3") (pinfunction "3_3") (pintype "passive"))
      (node (ref "J406") (pin "11") (pinfunction "11_11") (pintype "passive"))
      (node (ref "J407") (pin "3") (pinfunction "3_3") (pintype "passive"))
      (node (ref "S428") (pin "2") (pinfunction "2_2") (pintype "passive"))
      (node (ref "U401") (pin "28") (pinfunction "VDD(3V3)_28") (pintype "bidirectional"))
      (node (ref "U401") (pin "54") (pinfunction "VDD(3V3)_54") (pintype "bidirectional"))
      (node (ref "U401") (pin "71") (pinfunction "VDD(3V3)_71") (pintype "bidirectional"))
      (node (ref "U401") (pin "96") (pinfunction "VDD(3V3)_96") (pintype "bidirectional"))
    )
    (net (code "93") (name "/VDD(DCDC)") (class "Default")
      (node (ref "C103") (pin "1") (pinfunction "1_1") (pintype "passive"))
      (node (ref "C205") (pin "1") (pinfunction "1_1") (pintype "passive"))
      (node (ref "C413") (pin "1") (pinfunction "1_1") (pintype "passive"))
      (node (ref "C442") (pin "1") (pinfunction "1_1") (pintype "passive"))
      (node (ref "C484") (pin "1") (pinfunction "1_1") (pintype "passive"))
      (node (ref "J401") (pin "7") (pinfunction "7_7") (pintype "passive"))
      (node (ref "J403") (pin "5") (pinfunction "5_5") (pintype "passive"))
      (node (ref "J407") (pin "9") (pinfunction "9_9") (pintype "passive"))
      (node (ref "Q050") (pin "2") (pinfunction "S_2") (pintype "passive"))
      (node (ref "R051") (pin "1") (pinfunction "1_1") (pintype "passive"))
      (node (ref "R417") (pin "1") (pinfunction "1_1") (pintype "passive"))
      (node (ref "S410") (pin "2") (pinfunction "2_2") (pintype "passive"))
      (node (ref "S412") (pin "2") (pinfunction "2_2") (pintype "passive"))
      (node (ref "S419") (pin "2") (pinfunction "2_2") (pintype "passive"))
      (node (ref "S428") (pin "1") (pinfunction "1_1") (pintype "passive"))
      (node (ref "U101") (pin "3") (pinfunction "VCC_3") (pintype "bidirectional"))
      (node (ref "U201") (pin "5") (pinfunction "VOUT_5") (pintype "bidirectional"))
      (node (ref "U401") (pin "13") (pinfunction "VDD(DCDC)_13") (pintype "bidirectional"))
      (node (ref "U401") (pin "42") (pinfunction "VDD(DCDC)_42") (pintype "bidirectional"))
      (node (ref "U401") (pin "84") (pinfunction "VDD(DCDC)_84") (pintype "bidirectional"))
    )
    (net (code "94") (name "/VDDA") (class "Default")
      (node (ref "C410") (pin "1") (pinfunction "1_1") (pintype "passive"))
      (node (ref "J402") (pin "5") (pinfunction "5_5") (pintype "passive"))
      (node (ref "S410") (pin "1") (pinfunction "1_1") (pintype "passive"))
      (node (ref "U401") (pin "10") (pinfunction "VDDA_10") (pintype "bidirectional"))
      (node (ref "U501") (pin "1") (pinfunction "VCC_1") (pintype "bidirectional"))
    )
    (net (code "95") (name "/VIN+") (class "Default")
      (node (ref "D303") (pin "3") (pinfunction "K_3") (pintype "passive"))
      (node (ref "R105") (pin "1") (pinfunction "1_1") (pintype "passive"))
      (node (ref "U101") (pin "5") (pinfunction "RS+_5") (pintype "bidirectional"))
    )
    (net (code "96") (name "/VIN-") (class "Default")
      (node (ref "C201") (pin "1") (pinfunction "1_1") (pintype "passive"))
      (node (ref "R102") (pin "2") (pinfunction "2_2") (pintype "passive"))
      (node (ref "R105") (pin "2") (pinfunction "2_2") (pintype "passive"))
      (node (ref "S201") (pin "3") (pinfunction "P$2_3") (pintype "bidirectional"))
      (node (ref "U101") (pin "4") (pinfunction "RS-_4") (pintype "bidirectional"))
      (node (ref "U201") (pin "1") (pinfunction "VIN_1") (pintype "bidirectional"))
    )
    (net (code "97") (name "/VLIPO") (class "Default")
      (node (ref "C303") (pin "1") (pinfunction "1_1") (pintype "passive"))
      (node (ref "D303") (pin "2") (pinfunction "A2_2") (pintype "passive"))
      (node (ref "J301") (pin "2") (pinfunction "2_2") (pintype "passive"))
      (node (ref "U301") (pin "3") (pinfunction "VBAT_3") (pintype "power_in"))
    )
    (net (code "98") (name "/VREF") (class "Default")
      (node (ref "C412") (pin "1") (pinfunction "1_1") (pintype "passive"))
      (node (ref "J402") (pin "6") (pinfunction "6_6") (pintype "passive"))
      (node (ref "S412") (pin "1") (pinfunction "1_1") (pintype "passive"))
      (node (ref "U401") (pin "12") (pinfunction "VREF_12") (pintype "bidirectional"))
    )
    (net (code "99") (name "/XTAL1") (class "Default")
      (node (ref "C422") (pin "2") (pinfunction "2_2") (pintype "passive"))
      (node (ref "J402") (pin "11") (pinfunction "11_11") (pintype "passive"))
      (node (ref "U401") (pin "22") (pinfunction "XTAL1_22") (pintype "bidirectional"))
      (node (ref "Y422") (pin "1") (pinfunction "1_1") (pintype "passive"))
    )
    (net (code "100") (name "/XTAL2") (class "Default")
      (node (ref "C423") (pin "2") (pinfunction "2_2") (pintype "passive"))
      (node (ref "J401") (pin "12") (pinfunction "12_12") (pintype "passive"))
      (node (ref "U401") (pin "23") (pinfunction "XTAL2_23") (pintype "bidirectional"))
      (node (ref "Y422") (pin "3") (pinfunction "2_3") (pintype "passive"))
    )
    (net (code "101") (name "GND") (class "Default")
      (node (ref "C020") (pin "2") (pinfunction "2_2") (pintype "passive"))
      (node (ref "C030") (pin "2") (pinfunction "2_2") (pintype "passive"))
      (node (ref "C103") (pin "2") (pinfunction "2_2") (pintype "passive"))
      (node (ref "C201") (pin "2") (pinfunction "2_2") (pintype "passive"))
      (node (ref "C204") (pin "2") (pinfunction "2_2") (pintype "passive"))
      (node (ref "C205") (pin "2") (pinfunction "2_2") (pintype "passive"))
      (node (ref "C303") (pin "2") (pinfunction "2_2") (pintype "passive"))
      (node (ref "C304") (pin "2") (pinfunction "2_2") (pintype "passive"))
      (node (ref "C410") (pin "2") (pinfunction "2_2") (pintype "passive"))
      (node (ref "C412") (pin "2") (pinfunction "2_2") (pintype "passive"))
      (node (ref "C413") (pin "2") (pinfunction "2_2") (pintype "passive"))
      (node (ref "C416") (pin "1") (pinfunction "1_1") (pintype "passive"))
      (node (ref "C418") (pin "1") (pinfunction "1_1") (pintype "passive"))
      (node (ref "C419") (pin "2") (pinfunction "2_2") (pintype "passive"))
      (node (ref "C422") (pin "1") (pinfunction "1_1") (pintype "passive"))
      (node (ref "C423") (pin "1") (pinfunction "1_1") (pintype "passive"))
      (node (ref "C428") (pin "2") (pinfunction "2_2") (pintype "passive"))
      (node (ref "C442") (pin "2") (pinfunction "2_2") (pintype "passive"))
      (node (ref "C454") (pin "2") (pinfunction "2_2") (pintype "passive"))
      (node (ref "C471") (pin "2") (pinfunction "2_2") (pintype "passive"))
      (node (ref "C484") (pin "2") (pinfunction "2_2") (pintype "passive"))
      (node (ref "C496") (pin "2") (pinfunction "2_2") (pintype "passive"))
      (node (ref "C701") (pin "2") (pinfunction "2_2") (pintype "passive"))
      (node (ref "J001") (pin "5") (pinfunction "GND_5") (pintype "bidirectional"))
      (node (ref "J001") (pin "P$10") (pinfunction "GND_P$10") (pintype "bidirectional"))
      (node (ref "J001") (pin "P$11") (pinfunction "GND_P$11") (pintype "bidirectional"))
      (node (ref "J001") (pin "P$6") (pinfunction "GND_P$6") (pintype "bidirectional"))
      (node (ref "J001") (pin "P$7") (pinfunction "GND_P$7") (pintype "bidirectional"))
      (node (ref "J001") (pin "P$8") (pinfunction "GND_P$8") (pintype "bidirectional"))
      (node (ref "J001") (pin "P$9") (pinfunction "GND_P$9") (pintype "bidirectional"))
      (node (ref "J301") (pin "1") (pinfunction "1_1") (pintype "passive"))
      (node (ref "J401") (pin "8") (pinfunction "8_8") (pintype "passive"))
      (node (ref "J404") (pin "10") (pinfunction "10_10") (pintype "passive"))
      (node (ref "J404") (pin "5") (pinfunction "5_5") (pintype "passive"))
      (node (ref "J405") (pin "11") (pinfunction "11_11") (pintype "passive"))
      (node (ref "J406") (pin "2") (pinfunction "2_2") (pintype "passive"))
      (node (ref "J408") (pin "2") (pinfunction "2_2") (pintype "passive"))
      (node (ref "J408") (pin "9") (pinfunction "9_9") (pintype "passive"))
      (node (ref "J701") (pin "6") (pinfunction "GND_6") (pintype "bidirectional"))
      (node (ref "J701") (pin "CD2") (pinfunction "SHIELD_CD2") (pintype "bidirectional"))
      (node (ref "J701") (pin "GND1") (pinfunction "SHIELD_GND1") (pintype "bidirectional"))
      (node (ref "J701") (pin "GND3") (pinfunction "SHIELD_GND3") (pintype "bidirectional"))
      (node (ref "R011") (pin "1") (pinfunction "1_1") (pintype "passive"))
      (node (ref "R050") (pin "2") (pinfunction "2_2") (pintype "passive"))
      (node (ref "R101") (pin "1") (pinfunction "1_1") (pintype "passive"))
      (node (ref "R305") (pin "1") (pinfunction "1_1") (pintype "passive"))
      (node (ref "S001") (pin "1") (pinfunction "1_1") (pintype "passive"))
      (node (ref "S010") (pin "P$2") (pinfunction "2_P$2") (pintype "bidirectional"))
      (node (ref "S010") (pin "P$3") (pinfunction "1_P$3") (pintype "bidirectional"))
      (node (ref "S201") (pin "1") (pinfunction "P$1_1") (pintype "bidirectional"))
      (node (ref "S411") (pin "2") (pinfunction "2_2") (pintype "passive"))
      (node (ref "S417") (pin "P$2") (pinfunction "2_P$2") (pintype "bidirectional"))
      (node (ref "S417") (pin "P$3") (pinfunction "1_P$3") (pintype "bidirectional"))
      (node (ref "U101") (pin "1") (pinfunction "GND_1") (pintype "bidirectional"))
      (node (ref "U101") (pin "2") (pinfunction "GND_2") (pintype "bidirectional"))
      (node (ref "U201") (pin "2") (pinfunction "GND_2") (pintype "bidirectional"))
      (node (ref "U301") (pin "2") (pinfunction "VSS_2") (pintype "power_in"))
      (node (ref "U401") (pin "15") (pinfunction "GND_15") (pintype "bidirectional"))
      (node (ref "U401") (pin "31") (pinfunction "GND_31") (pintype "bidirectional"))
      (node (ref "U401") (pin "41") (pinfunction "GND_41") (pintype "bidirectional"))
      (node (ref "U401") (pin "55") (pinfunction "GND_55") (pintype "bidirectional"))
      (node (ref "U401") (pin "72") (pinfunction "GND_72") (pintype "bidirectional"))
      (node (ref "U401") (pin "83") (pinfunction "GND_83") (pintype "bidirectional"))
      (node (ref "U401") (pin "97") (pinfunction "GND_97") (pintype "bidirectional"))
      (node (ref "Y422") (pin "2") (pinfunction "GND_2") (pintype "passive"))
      (node (ref "Y422") (pin "4") (pinfunction "GND_4") (pintype "passive"))
    )
    (net (code "102") (name "Net-(D050-PadC)") (class "Default")
      (node (ref "D050") (pin "C") (pinfunction "C_C") (pintype "passive"))
      (node (ref "R050") (pin "1") (pinfunction "1_1") (pintype "passive"))
    )
    (net (code "103") (name "Net-(D301-PadA)") (class "Default")
      (node (ref "D301") (pin "A") (pinfunction "A_A") (pintype "passive"))
      (node (ref "R304") (pin "1") (pinfunction "1_1") (pintype "passive"))
    )
    (net (code "104") (name "Net-(J001-D+)") (class "Default")
      (node (ref "J001") (pin "3") (pinfunction "D+_3") (pintype "bidirectional"))
      (node (ref "R030") (pin "2") (pinfunction "2_2") (pintype "passive"))
      (node (ref "R031") (pin "2") (pinfunction "2_2") (pintype "passive"))
    )
    (net (code "105") (name "Net-(J001-D-)") (class "Default")
      (node (ref "J001") (pin "2") (pinfunction "D-_2") (pintype "bidirectional"))
      (node (ref "R020") (pin "2") (pinfunction "2_2") (pintype "passive"))
    )
    (net (code "106") (name "Net-(Q050-D)") (class "Default")
      (node (ref "D050") (pin "A") (pinfunction "A_A") (pintype "passive"))
      (node (ref "Q050") (pin "3") (pinfunction "D_3") (pintype "passive"))
      (node (ref "R031") (pin "1") (pinfunction "1_1") (pintype "passive"))
    )
    (net (code "107") (name "Net-(S201A-P$3)") (class "Default")
      (node (ref "S201") (pin "2") (pinfunction "P$3_2") (pintype "bidirectional"))
      (node (ref "U201") (pin "3") (pinfunction "EN_3") (pintype "bidirectional"))
    )
    (net (code "108") (name "Net-(U201-BYP)") (class "Default")
      (node (ref "C204") (pin "1") (pinfunction "1_1") (pintype "passive"))
      (node (ref "U201") (pin "4") (pinfunction "BYP_4") (pintype "bidirectional"))
    )
    (net (code "109") (name "Net-(U301-PROG)") (class "Default")
      (node (ref "R305") (pin "2") (pinfunction "2_2") (pintype "passive"))
      (node (ref "U301") (pin "5") (pinfunction "PROG_5") (pintype "passive"))
    )
    (net (code "110") (name "Net-(U301-STAT)") (class "Default")
      (node (ref "D301") (pin "C") (pinfunction "C_C") (pintype "passive"))
      (node (ref "U301") (pin "1") (pinfunction "STAT_1") (pintype "bidirectional"))
    )
    (net (code "111") (name "unconnected-(J701-CD-PadCD1)") (class "Default")
      (node (ref "J701") (pin "CD1") (pinfunction "CD_CD1") (pintype "bidirectional"))
    )
  )
)
